# USB_TO_IO_SCH_V102.net
KiCad netlist of a schematic drawn in Altium Designer
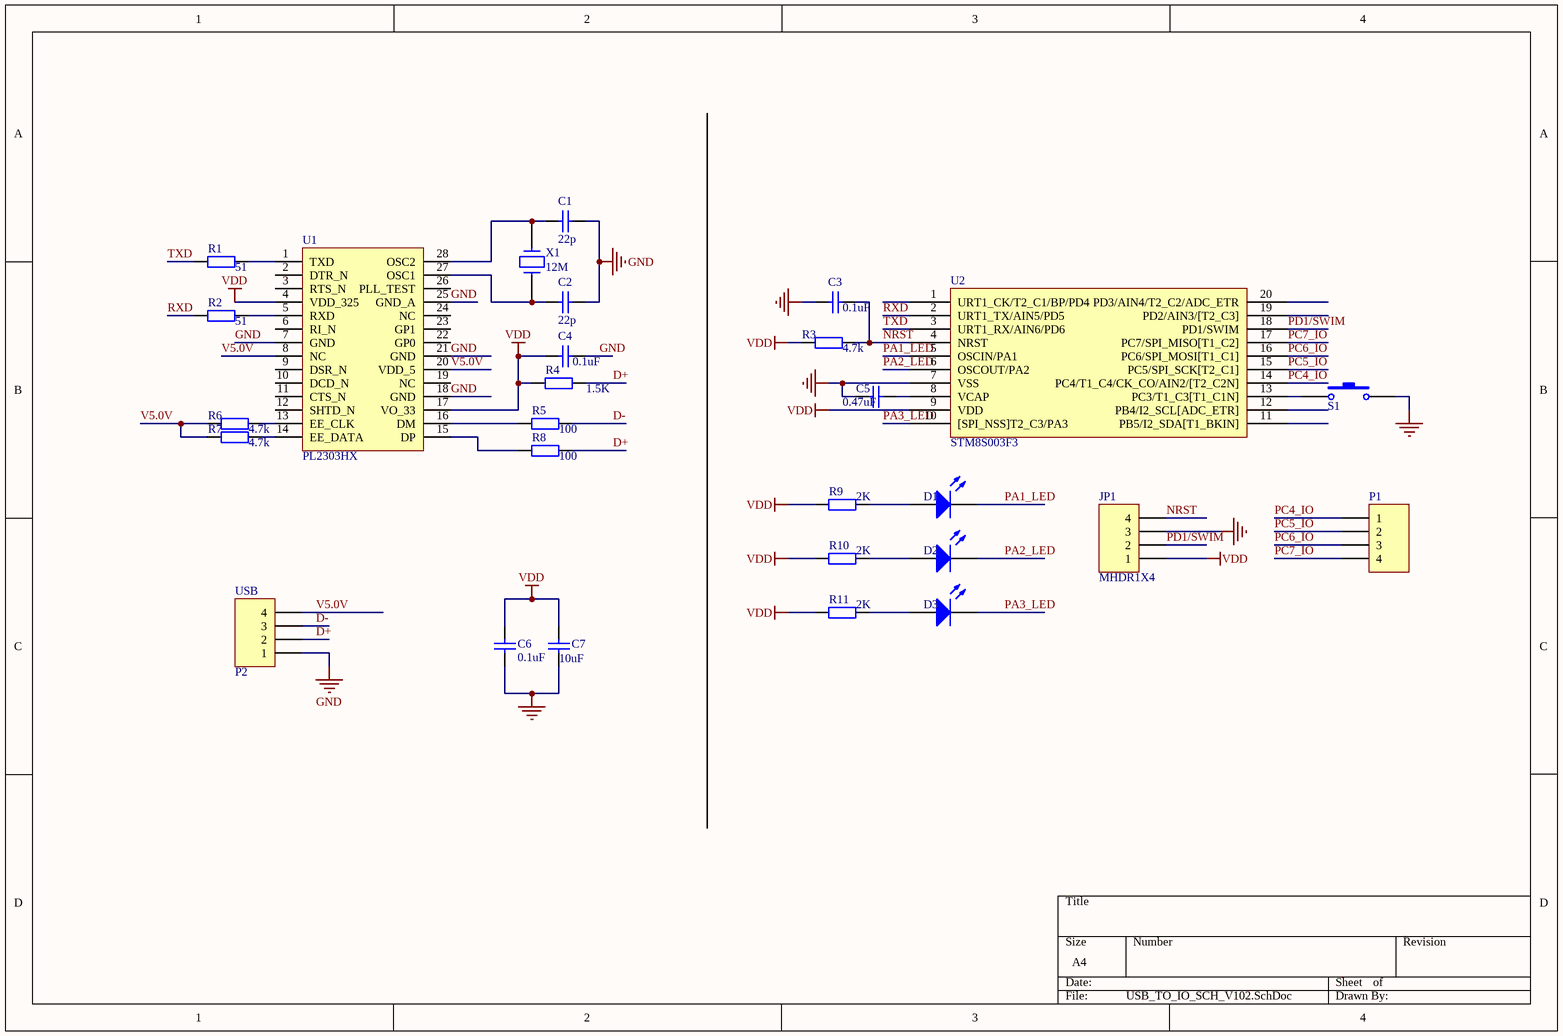
[diagram p0: USB_TO_IO_SCH_V102.SchDoc]

(export (version "E")
  (design (tool "Eeschema 10.0.6"))
  (components
    (comp (ref "C1")
      (value "22p")
      (footprint "CS0603")
      (fields (field (name "Comment") "Cap_0603"))
      (libsource (lib "MY_Library") (part "cap"))
    )
    (comp (ref "C2")
      (value "22p")
      (footprint "CS0603")
      (fields (field (name "Comment") "Cap_0603"))
      (libsource (lib "MY_Library") (part "cap"))
    )
    (comp (ref "C3")
      (value "0.1uF")
      (footprint "CS0603")
      (fields (field (name "Comment") "Cap_0603"))
      (libsource (lib "MY_Library") (part "cap"))
    )
    (comp (ref "C4")
      (value "0.1uF")
      (footprint "CS0603")
      (fields (field (name "Comment") "Cap_0603"))
      (libsource (lib "MY_Library") (part "cap"))
    )
    (comp (ref "C5")
      (value "0.47uF")
      (footprint "CS0603")
      (fields (field (name "Comment") "Cap_0603"))
      (libsource (lib "MY_Library") (part "cap"))
    )
    (comp (ref "C6")
      (value "0.1uF")
      (footprint "CS0603")
      (fields (field (name "Comment") "Cap_0603"))
      (libsource (lib "MY_Library") (part "cap"))
    )
    (comp (ref "C7")
      (value "10uF")
      (footprint "CAP_8050")
      (fields (field (name "Comment") "Cap_0603"))
      (libsource (lib "MY_Library") (part "cap"))
    )
    (comp (ref "D1") (value "LED") (footprint "LED_0603") (libsource (lib "MY_Library") (part "LED0")))
    (comp (ref "D2") (value "LED") (footprint "LED_0603") (libsource (lib "MY_Library") (part "LED0")))
    (comp (ref "D3") (value "LED") (footprint "LED_0603") (libsource (lib "MY_Library") (part "LED0")))
    (comp (ref "JP1")
      (value "MHDR1X4")
      (footprint "MHDR1X4")
      (description "Header, 4-Pin")
      (fields (field (name "PUBLISHER") "Altium Limited"))
      (libsource (lib "Miscellaneous Connectors") (part "MHDR1X4"))
    )
    (comp (ref "P1") (value "Header 4") (footprint "HDR1X4") (libsource (lib "MY_Library") (part "Header 4")))
    (comp (ref "P2") (value "USB") (footprint "USB_M") (libsource (lib "") (part "Header 4_1")))
    (comp (ref "R1")
      (value "51")
      (footprint "S0603")
      (fields (field (name "Comment") "Reg_0603"))
      (libsource (lib "MY_Library") (part "Register"))
    )
    (comp (ref "R2")
      (value "51")
      (footprint "S0603")
      (fields (field (name "Comment") "Reg_0603"))
      (libsource (lib "MY_Library") (part "Register"))
    )
    (comp (ref "R3")
      (value "4.7k")
      (footprint "S0603")
      (fields (field (name "Comment") "Reg_0603"))
      (libsource (lib "MY_Library") (part "Register"))
    )
    (comp (ref "R4")
      (value "1.5K")
      (footprint "S0603")
      (fields (field (name "Comment") "Reg_0603"))
      (libsource (lib "MY_Library") (part "Register"))
    )
    (comp (ref "R5")
      (value "100")
      (footprint "S0603")
      (fields (field (name "Comment") "Reg_0603"))
      (libsource (lib "MY_Library") (part "Register"))
    )
    (comp (ref "R6")
      (value "4.7k")
      (footprint "S0603")
      (fields (field (name "Comment") "Reg_0603"))
      (libsource (lib "MY_Library") (part "Register"))
    )
    (comp (ref "R7")
      (value "4.7k")
      (footprint "S0603")
      (fields (field (name "Comment") "Reg_0603"))
      (libsource (lib "MY_Library") (part "Register"))
    )
    (comp (ref "R8")
      (value "100")
      (footprint "S0603")
      (fields (field (name "Comment") "Reg_0603"))
      (libsource (lib "MY_Library") (part "Register"))
    )
    (comp (ref "R9")
      (value "2K")
      (footprint "S0603")
      (fields (field (name "Comment") "Reg_0603"))
      (libsource (lib "MY_Library") (part "Register"))
    )
    (comp (ref "R10")
      (value "2K")
      (footprint "S0603")
      (fields (field (name "Comment") "Reg_0603"))
      (libsource (lib "MY_Library") (part "Register"))
    )
    (comp (ref "R11")
      (value "2K")
      (footprint "S0603")
      (fields (field (name "Comment") "Reg_0603"))
      (libsource (lib "MY_Library") (part "Register"))
    )
    (comp (ref "S1") (value "SW") (footprint "SWITCH-2") (libsource (lib "MY_Library") (part "SW")))
    (comp (ref "U1") (value "PL2303HX") (footprint "SSOP28") (libsource (lib "MY_Library") (part "PL2303HX")))
    (comp (ref "U2")
      (value "STM8S003F3")
      (footprint "STM8S003F3")
      (libsource (lib "MY_Library") (part "STM8S003F3"))
    )
    (comp (ref "X1")
      (value "12M")
      (footprint "XATL")
      (fields (field (name "Comment") "CRYSTAL"))
      (libsource (lib "MY_Library") (part "CRYSTAL"))
    )
  )
  (nets
    (net (code "1") (name "/D+") (class "Default")
      (node (ref "P2") (pin "2") (pinfunction "2_2") (pintype "passive"))
      (node (ref "R4") (pin "2") (pinfunction "2_2") (pintype "passive"))
      (node (ref "R8") (pin "2") (pinfunction "2_2") (pintype "passive"))
    )
    (net (code "2") (name "/D-") (class "Default")
      (node (ref "P2") (pin "3") (pinfunction "3_3") (pintype "passive"))
      (node (ref "R5") (pin "2") (pinfunction "2_2") (pintype "passive"))
    )
    (net (code "3") (name "/NRST") (class "Default")
      (node (ref "C3") (pin "2") (pinfunction "2_2") (pintype "passive"))
      (node (ref "JP1") (pin "4") (pinfunction "4_4") (pintype "passive"))
      (node (ref "R3") (pin "2") (pinfunction "2_2") (pintype "passive"))
      (node (ref "U2") (pin "4") (pinfunction "NRST_4") (pintype "passive"))
    )
    (net (code "4") (name "/PA1_LED") (class "Default")
      (node (ref "D1") (pin "2") (pinfunction "K_2") (pintype "passive"))
      (node (ref "U2") (pin "5") (pinfunction "OSCIN/PA1_5") (pintype "passive"))
    )
    (net (code "5") (name "/PA2_LED") (class "Default")
      (node (ref "D2") (pin "2") (pinfunction "K_2") (pintype "passive"))
      (node (ref "U2") (pin "6") (pinfunction "OSCOUT/PA2_6") (pintype "passive"))
    )
    (net (code "6") (name "/PA3_LED") (class "Default")
      (node (ref "D3") (pin "2") (pinfunction "K_2") (pintype "passive"))
      (node (ref "U2") (pin "10") (pinfunction "[SPI_NSS]T2_C3/PA3_10") (pintype "passive"))
    )
    (net (code "7") (name "/PC4_IO") (class "Default")
      (node (ref "P1") (pin "1") (pinfunction "1_1") (pintype "passive"))
      (node (ref "U2") (pin "14") (pinfunction "PC4/T1_C4/CK_CO/AIN2/[T2_C2N]_14") (pintype "passive"))
    )
    (net (code "8") (name "/PC5_IO") (class "Default")
      (node (ref "P1") (pin "2") (pinfunction "2_2") (pintype "passive"))
      (node (ref "U2") (pin "15") (pinfunction "PC5/SPI_SCK[T2_C1]_15") (pintype "passive"))
    )
    (net (code "9") (name "/PC6_IO") (class "Default")
      (node (ref "P1") (pin "3") (pinfunction "3_3") (pintype "passive"))
      (node (ref "U2") (pin "16") (pinfunction "PC6/SPI_MOSI[T1_C1]_16") (pintype "passive"))
    )
    (net (code "10") (name "/PC7_IO") (class "Default")
      (node (ref "P1") (pin "4") (pinfunction "4_4") (pintype "passive"))
      (node (ref "U2") (pin "17") (pinfunction "PC7/SPI_MISO[T1_C2]_17") (pintype "passive"))
    )
    (net (code "11") (name "/PD1{slash}SWIM") (class "Default")
      (node (ref "JP1") (pin "2") (pinfunction "2_2") (pintype "passive"))
      (node (ref "U2") (pin "18") (pinfunction "PD1/SWIM_18") (pintype "passive"))
    )
    (net (code "12") (name "/RXD") (class "Default")
      (node (ref "R2") (pin "1") (pinfunction "1_1") (pintype "passive"))
      (node (ref "U2") (pin "2") (pinfunction "URT1_TX/AIN5/PD5_2") (pintype "passive"))
    )
    (net (code "13") (name "/TXD") (class "Default")
      (node (ref "R1") (pin "1") (pinfunction "1_1") (pintype "passive"))
      (node (ref "U2") (pin "3") (pinfunction "URT1_RX/AIN6/PD6_3") (pintype "passive"))
    )
    (net (code "14") (name "/V5.0V") (class "Default")
      (node (ref "P2") (pin "4") (pinfunction "4_4") (pintype "passive"))
      (node (ref "R6") (pin "1") (pinfunction "1_1") (pintype "passive"))
      (node (ref "R7") (pin "1") (pinfunction "1_1") (pintype "passive"))
      (node (ref "U1") (pin "20") (pinfunction "VDD_5_20") (pintype "passive"))
      (node (ref "U1") (pin "8") (pinfunction "NC_8") (pintype "passive"))
    )
    (net (code "15") (name "GND") (class "Default")
      (node (ref "C1") (pin "2") (pinfunction "2_2") (pintype "passive"))
      (node (ref "C2") (pin "2") (pinfunction "2_2") (pintype "passive"))
      (node (ref "C3") (pin "1") (pinfunction "1_1") (pintype "passive"))
      (node (ref "C4") (pin "2") (pinfunction "2_2") (pintype "passive"))
      (node (ref "C5") (pin "1") (pinfunction "1_1") (pintype "passive"))
      (node (ref "C6") (pin "1") (pinfunction "1_1") (pintype "passive"))
      (node (ref "C7") (pin "1") (pinfunction "1_1") (pintype "passive"))
      (node (ref "JP1") (pin "3") (pinfunction "3_3") (pintype "passive"))
      (node (ref "P2") (pin "1") (pinfunction "1_1") (pintype "passive"))
      (node (ref "S1") (pin "2") (pinfunction "2_2") (pintype "passive"))
      (node (ref "U1") (pin "18") (pinfunction "GND_18") (pintype "passive"))
      (node (ref "U1") (pin "21") (pinfunction "GND_21") (pintype "passive"))
      (node (ref "U1") (pin "25") (pinfunction "GND_A_25") (pintype "passive"))
      (node (ref "U1") (pin "7") (pinfunction "GND_7") (pintype "passive"))
      (node (ref "U2") (pin "7") (pinfunction "VSS_7") (pintype "passive"))
    )
    (net (code "16") (name "Net-(D1-A)") (class "Default")
      (node (ref "D1") (pin "1") (pinfunction "A_1") (pintype "passive"))
      (node (ref "R9") (pin "2") (pinfunction "2_2") (pintype "passive"))
    )
    (net (code "17") (name "Net-(D2-A)") (class "Default")
      (node (ref "D2") (pin "1") (pinfunction "A_1") (pintype "passive"))
      (node (ref "R10") (pin "2") (pinfunction "2_2") (pintype "passive"))
    )
    (net (code "18") (name "Net-(D3-A)") (class "Default")
      (node (ref "D3") (pin "1") (pinfunction "A_1") (pintype "passive"))
      (node (ref "R11") (pin "2") (pinfunction "2_2") (pintype "passive"))
    )
    (net (code "19") (name "Net-(U1-DM)") (class "Default")
      (node (ref "R5") (pin "1") (pinfunction "1_1") (pintype "passive"))
      (node (ref "U1") (pin "16") (pinfunction "DM_16") (pintype "passive"))
    )
    (net (code "20") (name "Net-(U1-DP)") (class "Default")
      (node (ref "R8") (pin "1") (pinfunction "1_1") (pintype "passive"))
      (node (ref "U1") (pin "15") (pinfunction "DP_15") (pintype "passive"))
    )
    (net (code "21") (name "Net-(U1-EE_CLK)") (class "Default")
      (node (ref "R6") (pin "2") (pinfunction "2_2") (pintype "passive"))
      (node (ref "U1") (pin "13") (pinfunction "EE_CLK_13") (pintype "passive"))
    )
    (net (code "22") (name "Net-(U1-EE_DATA)") (class "Default")
      (node (ref "R7") (pin "2") (pinfunction "2_2") (pintype "passive"))
      (node (ref "U1") (pin "14") (pinfunction "EE_DATA_14") (pintype "passive"))
    )
    (net (code "23") (name "Net-(U1-OSC1)") (class "Default")
      (node (ref "C2") (pin "1") (pinfunction "1_1") (pintype "passive"))
      (node (ref "U1") (pin "27") (pinfunction "OSC1_27") (pintype "passive"))
      (node (ref "X1") (pin "1") (pinfunction "1_1") (pintype "passive"))
    )
    (net (code "24") (name "Net-(U1-OSC2)") (class "Default")
      (node (ref "C1") (pin "1") (pinfunction "1_1") (pintype "passive"))
      (node (ref "U1") (pin "28") (pinfunction "OSC2_28") (pintype "passive"))
      (node (ref "X1") (pin "2") (pinfunction "2_2") (pintype "passive"))
    )
    (net (code "25") (name "Net-(U1-RXD)") (class "Default")
      (node (ref "R2") (pin "2") (pinfunction "2_2") (pintype "passive"))
      (node (ref "U1") (pin "5") (pinfunction "RXD_5") (pintype "passive"))
    )
    (net (code "26") (name "Net-(U1-TXD)") (class "Default")
      (node (ref "R1") (pin "2") (pinfunction "2_2") (pintype "passive"))
      (node (ref "U1") (pin "1") (pinfunction "TXD_1") (pintype "passive"))
    )
    (net (code "27") (name "Net-(U2-PC3{slash}T1_C3[T1_C1N])") (class "Default")
      (node (ref "S1") (pin "1") (pinfunction "1_1") (pintype "passive"))
      (node (ref "U2") (pin "13") (pinfunction "PC3/T1_C3[T1_C1N]_13") (pintype "passive"))
    )
    (net (code "28") (name "Net-(U2-VCAP)") (class "Default")
      (node (ref "C5") (pin "2") (pinfunction "2_2") (pintype "passive"))
      (node (ref "U2") (pin "8") (pinfunction "VCAP_8") (pintype "passive"))
    )
    (net (code "29") (name "VDD") (class "Default")
      (node (ref "C4") (pin "1") (pinfunction "1_1") (pintype "passive"))
      (node (ref "C6") (pin "2") (pinfunction "2_2") (pintype "passive"))
      (node (ref "C7") (pin "2") (pinfunction "2_2") (pintype "passive"))
      (node (ref "JP1") (pin "1") (pinfunction "1_1") (pintype "passive"))
      (node (ref "R10") (pin "1") (pinfunction "1_1") (pintype "passive"))
      (node (ref "R11") (pin "1") (pinfunction "1_1") (pintype "passive"))
      (node (ref "R3") (pin "1") (pinfunction "1_1") (pintype "passive"))
      (node (ref "R4") (pin "1") (pinfunction "1_1") (pintype "passive"))
      (node (ref "R9") (pin "1") (pinfunction "1_1") (pintype "passive"))
      (node (ref "U1") (pin "17") (pinfunction "VO_33_17") (pintype "passive"))
      (node (ref "U1") (pin "4") (pinfunction "VDD_325_4") (pintype "passive"))
      (node (ref "U2") (pin "9") (pinfunction "VDD_9") (pintype "passive"))
    )
    (net (code "30") (name "unconnected-(U1-CTS_N-Pad11)") (class "Default")
      (node (ref "U1") (pin "11") (pinfunction "CTS_N_11") (pintype "passive"))
    )
    (net (code "31") (name "unconnected-(U1-DCD_N-Pad10)") (class "Default")
      (node (ref "U1") (pin "10") (pinfunction "DCD_N_10") (pintype "passive"))
    )
    (net (code "32") (name "unconnected-(U1-DSR_N-Pad9)") (class "Default")
      (node (ref "U1") (pin "9") (pinfunction "DSR_N_9") (pintype "passive"))
    )
    (net (code "33") (name "unconnected-(U1-DTR_N-Pad2)") (class "Default")
      (node (ref "U1") (pin "2") (pinfunction "DTR_N_2") (pintype "passive"))
    )
    (net (code "34") (name "unconnected-(U1-GP0-Pad22)") (class "Default")
      (node (ref "U1") (pin "22") (pinfunction "GP0_22") (pintype "passive"))
    )
    (net (code "35") (name "unconnected-(U1-GP1-Pad23)") (class "Default")
      (node (ref "U1") (pin "23") (pinfunction "GP1_23") (pintype "passive"))
    )
    (net (code "36") (name "unconnected-(U1-NC-Pad19)") (class "Default")
      (node (ref "U1") (pin "19") (pinfunction "NC_19") (pintype "passive"))
    )
    (net (code "37") (name "unconnected-(U1-NC-Pad24)") (class "Default")
      (node (ref "U1") (pin "24") (pinfunction "NC_24") (pintype "passive"))
    )
    (net (code "38") (name "unconnected-(U1-PLL_TEST-Pad26)") (class "Default")
      (node (ref "U1") (pin "26") (pinfunction "PLL_TEST_26") (pintype "passive"))
    )
    (net (code "39") (name "unconnected-(U1-RI_N-Pad6)") (class "Default")
      (node (ref "U1") (pin "6") (pinfunction "RI_N_6") (pintype "passive"))
    )
    (net (code "40") (name "unconnected-(U1-RTS_N-Pad3)") (class "Default")
      (node (ref "U1") (pin "3") (pinfunction "RTS_N_3") (pintype "passive"))
    )
    (net (code "41") (name "unconnected-(U1-SHTD_N-Pad12)") (class "Default")
      (node (ref "U1") (pin "12") (pinfunction "SHTD_N_12") (pintype "passive"))
    )
    (net (code "42") (name "unconnected-(U2-PB4{slash}I2_SCL[ADC_ETR]-Pad12)") (class "Default")
      (node (ref "U2") (pin "12") (pinfunction "PB4/I2_SCL[ADC_ETR]_12") (pintype "passive"))
    )
    (net (code "43") (name "unconnected-(U2-PB5{slash}I2_SDA[T1_BKIN]-Pad11)") (class "Default")
      (node (ref "U2") (pin "11") (pinfunction "PB5/I2_SDA[T1_BKIN]_11") (pintype "passive"))
    )
    (net (code "44") (name "unconnected-(U2-PD2{slash}AIN3{slash}[T2_C3]-Pad19)") (class "Default")
      (node (ref "U2") (pin "19") (pinfunction "PD2/AIN3/[T2_C3]_19") (pintype "passive"))
    )
    (net (code "45") (name "unconnected-(U2-PD3{slash}AIN4{slash}T2_C2{slash}ADC_ETR-Pad20)") (class "Default")
      (node (ref "U2") (pin "20") (pinfunction "PD3/AIN4/T2_C2/ADC_ETR_20") (pintype "passive"))
    )
    (net (code "46") (name "unconnected-(U2-URT1_CK{slash}T2_C1{slash}BP{slash}PD4-Pad1)") (class "Default")
      (node (ref "U2") (pin "1") (pinfunction "URT1_CK/T2_C1/BP/PD4_1") (pintype "passive"))
    )
  )
)
